# 1-Schematic_STM_CC_RAINSUN_BASICONLY.net
KiCad netlist of a schematic drawn in EasyEDA
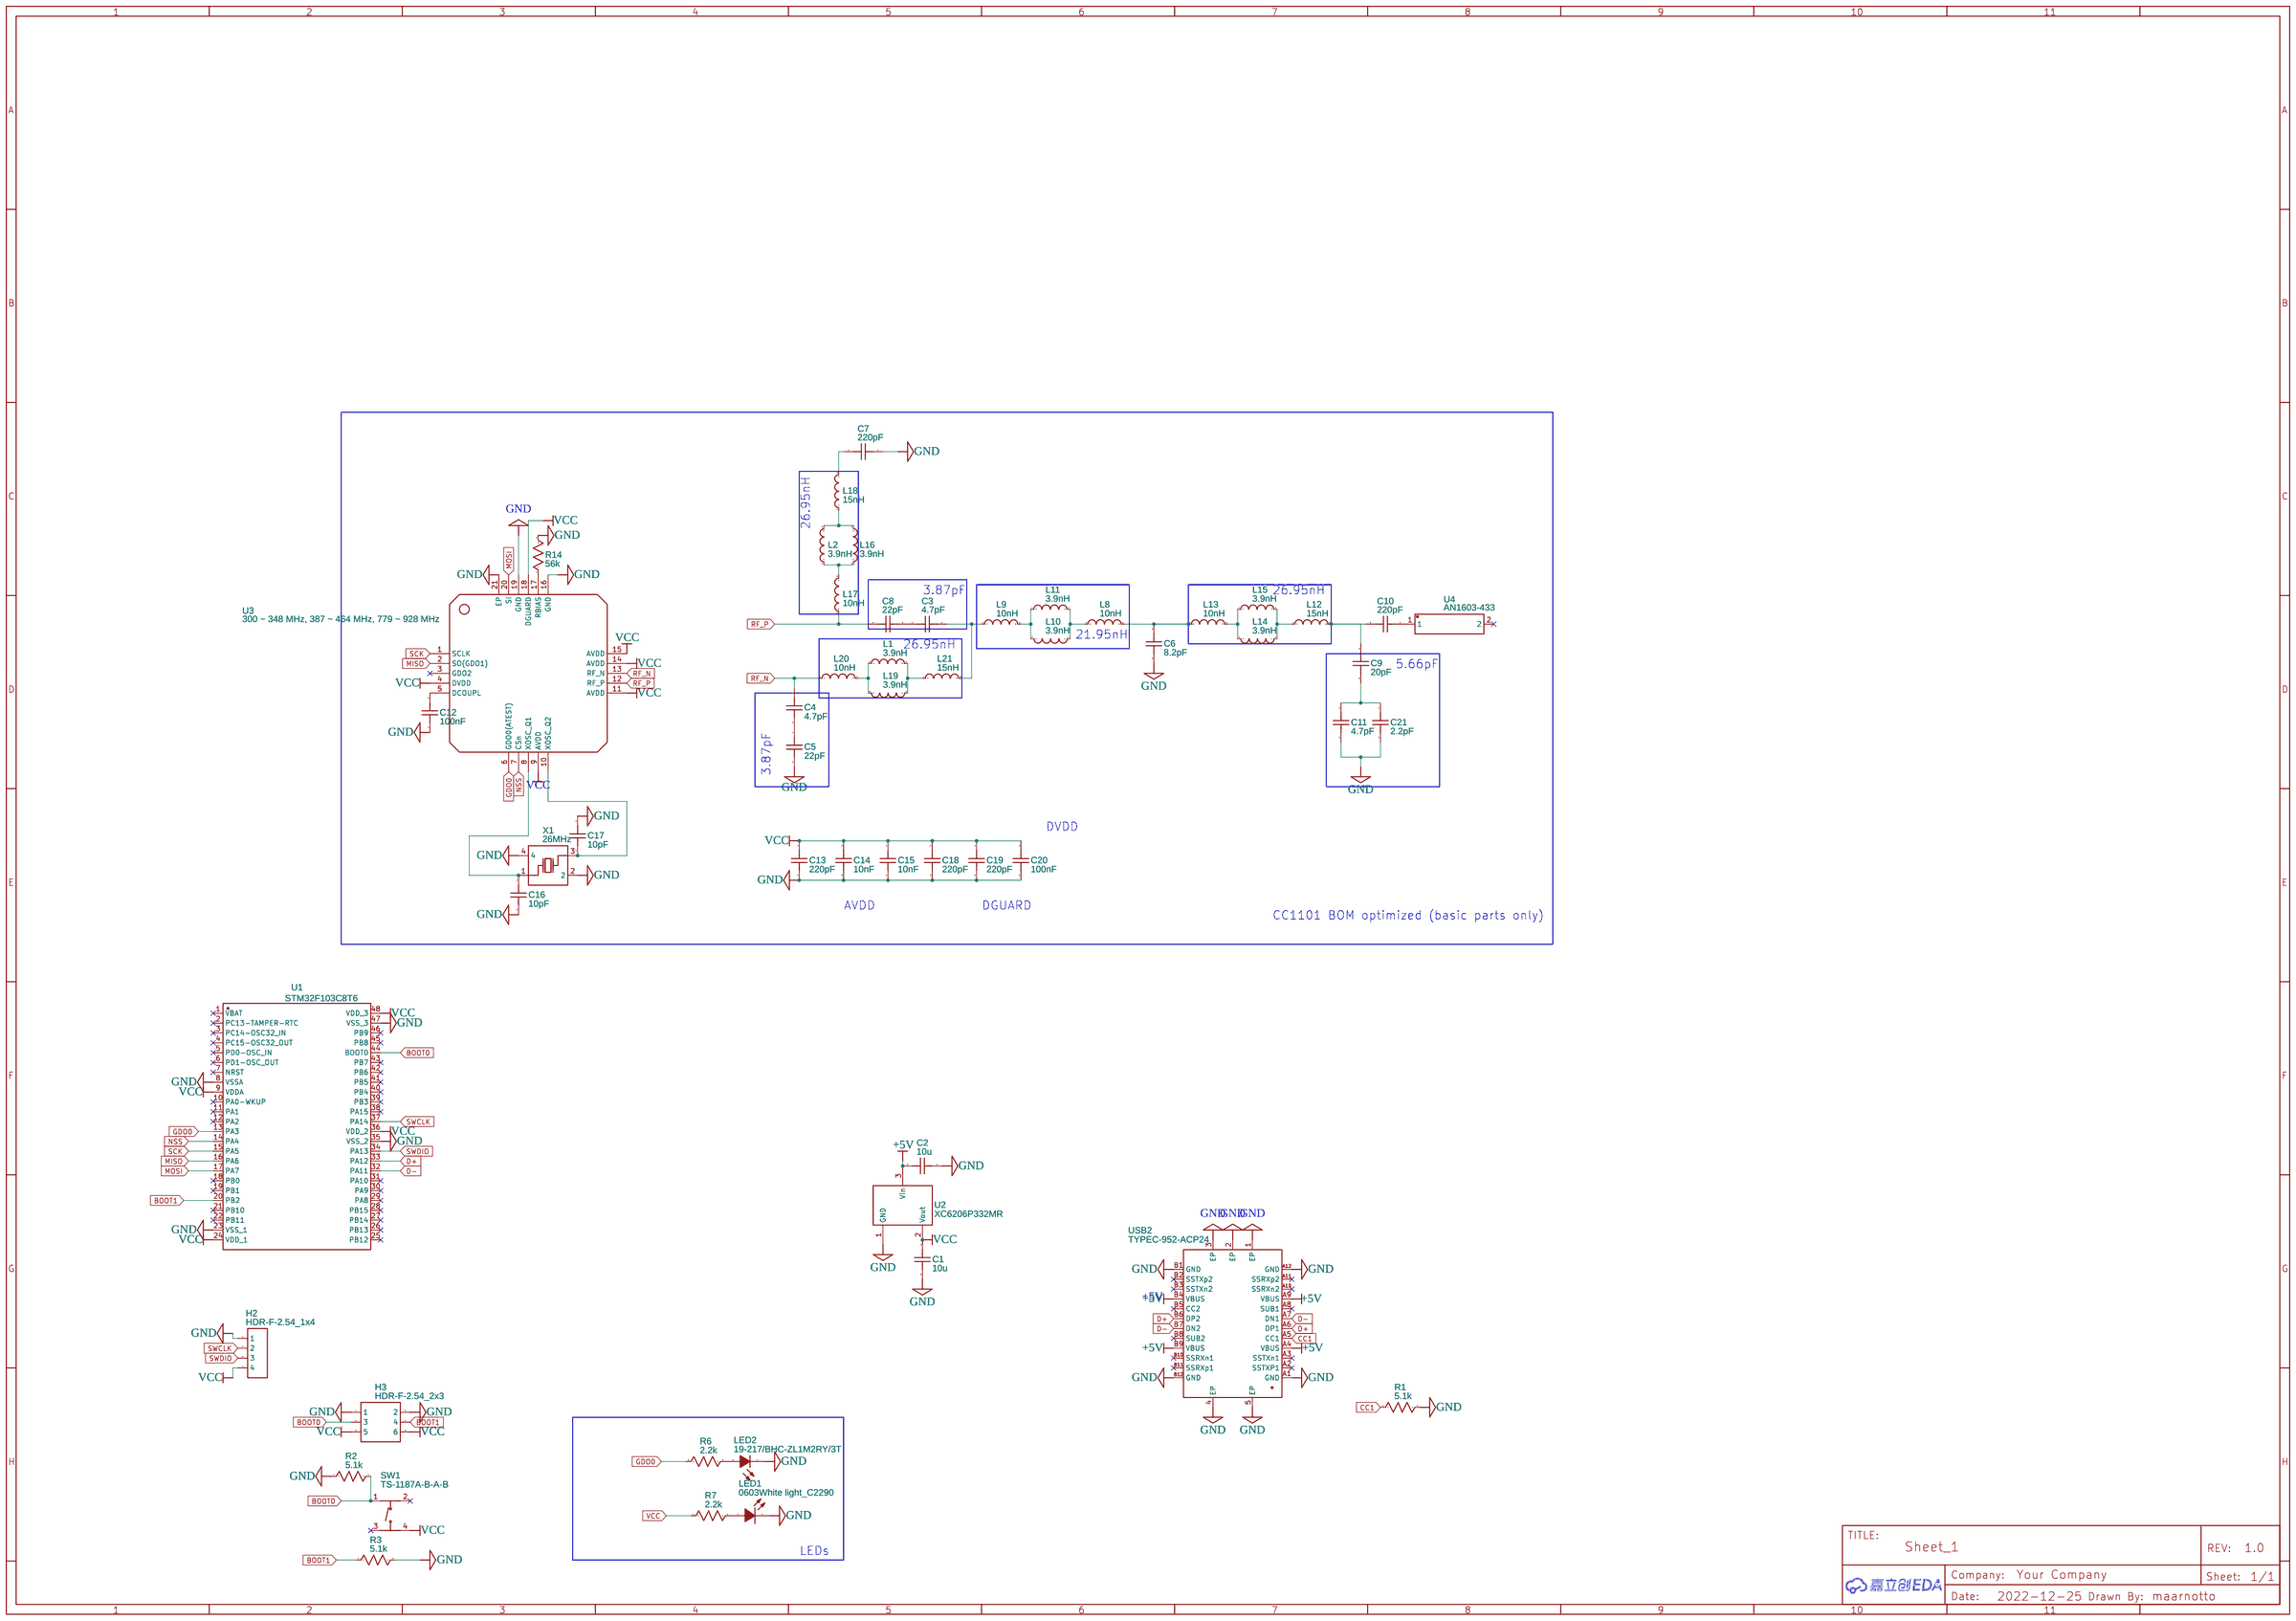
[diagram p0: schematic sheet]

(export (version "E")
  (design (tool "Eeschema 10.0.6"))
  (components
    (comp (ref "C1") (value "10u") (libsource (lib "") (part "C_0603_US")))
    (comp (ref "C2") (value "10u") (libsource (lib "") (part "C_0603_US_1")))
    (comp (ref "C3") (value "4.7pF") (libsource (lib "") (part "C_0402_US_1")))
    (comp (ref "C4") (value "4.7pF") (libsource (lib "") (part "C_0402_US")))
    (comp (ref "C5") (value "22pF") (libsource (lib "") (part "C_0402_US")))
    (comp (ref "C6") (value "8.2pF") (libsource (lib "") (part "C_0603_US")))
    (comp (ref "C7") (value "220pF") (libsource (lib "") (part "C_0402_US_1")))
    (comp (ref "C8") (value "22pF") (libsource (lib "") (part "C_0402_US_1")))
    (comp (ref "C9") (value "20pF") (libsource (lib "") (part "C_0402_US")))
    (comp (ref "C10") (value "220pF") (libsource (lib "") (part "C_0402_US_1")))
    (comp (ref "C11") (value "4.7pF") (libsource (lib "") (part "C_0402_US")))
    (comp (ref "C12") (value "100nF") (libsource (lib "") (part "C_0402_US")))
    (comp (ref "C13") (value "220pF") (libsource (lib "") (part "C_0402_US")))
    (comp (ref "C14") (value "10nF") (libsource (lib "") (part "C_0402_US")))
    (comp (ref "C15") (value "10nF") (libsource (lib "") (part "C_0402_US")))
    (comp (ref "C16") (value "10pF") (libsource (lib "") (part "C_0402_US")))
    (comp (ref "C17") (value "10pF") (libsource (lib "") (part "C_0402_US_2")))
    (comp (ref "C18") (value "220pF") (libsource (lib "") (part "C_0402_US")))
    (comp (ref "C19") (value "220pF") (libsource (lib "") (part "C_0402_US")))
    (comp (ref "C20") (value "100nF") (libsource (lib "") (part "C_0402_US")))
    (comp (ref "C21") (value "2.2pF") (libsource (lib "") (part "C_0402_US")))
    (comp (ref "H2")
      (value "HDR-F-2.54_1x4")
      (fields (field (name "BOM_Supplier Part") "C225501"))
      (libsource (lib "") (part "HDR-F-2.54_1x4"))
    )
    (comp (ref "H3")
      (value "HDR-F-2.54_2x3")
      (fields (field (name "BOM_Supplier Part") "C65114"))
      (libsource (lib "") (part "HDR-F-2.54_2x3"))
    )
    (comp (ref "L1")
      (value "3.9nH")
      (fields (field (name "BOM_Supplier Part") "C14033"))
      (libsource (lib "") (part "L0402_US_3"))
    )
    (comp (ref "L2")
      (value "3.9nH")
      (fields (field (name "BOM_Supplier Part") "C14033"))
      (libsource (lib "") (part "L0402_US_4"))
    )
    (comp (ref "L8")
      (value "10nH")
      (fields (field (name "BOM_Supplier Part") "C27147"))
      (libsource (lib "") (part "L0402_US_1"))
    )
    (comp (ref "L9")
      (value "10nH")
      (fields (field (name "BOM_Supplier Part") "C27147"))
      (libsource (lib "") (part "L0402_US_3"))
    )
    (comp (ref "L10")
      (value "3.9nH")
      (fields (field (name "BOM_Supplier Part") "C14033"))
      (libsource (lib "") (part "L0402_US"))
    )
    (comp (ref "L11")
      (value "3.9nH")
      (fields (field (name "BOM_Supplier Part") "C14033"))
      (libsource (lib "") (part "L0402_US_1"))
    )
    (comp (ref "L12")
      (value "15nH")
      (fields (field (name "BOM_Supplier Part") "C27143"))
      (libsource (lib "") (part "L0402_US_1"))
    )
    (comp (ref "L13")
      (value "10nH")
      (fields (field (name "BOM_Supplier Part") "C27147"))
      (libsource (lib "") (part "L0402_US_1"))
    )
    (comp (ref "L14")
      (value "3.9nH")
      (fields (field (name "BOM_Supplier Part") "C14033"))
      (libsource (lib "") (part "L0402_US"))
    )
    (comp (ref "L15")
      (value "3.9nH")
      (fields (field (name "BOM_Supplier Part") "C14033"))
      (libsource (lib "") (part "L0402_US_1"))
    )
    (comp (ref "L16")
      (value "3.9nH")
      (fields (field (name "BOM_Supplier Part") "C14033"))
      (libsource (lib "") (part "L0402_US_2"))
    )
    (comp (ref "L17")
      (value "10nH")
      (fields (field (name "BOM_Supplier Part") "C27147"))
      (libsource (lib "") (part "L0402_US_4"))
    )
    (comp (ref "L18")
      (value "15nH")
      (fields (field (name "BOM_Supplier Part") "C27143"))
      (libsource (lib "") (part "L0402_US_4"))
    )
    (comp (ref "L19")
      (value "3.9nH")
      (fields (field (name "BOM_Supplier Part") "C14033"))
      (libsource (lib "") (part "L0402_US_5"))
    )
    (comp (ref "L20")
      (value "10nH")
      (fields (field (name "BOM_Supplier Part") "C27147"))
      (libsource (lib "") (part "L0402_US_3"))
    )
    (comp (ref "L21")
      (value "15nH")
      (fields (field (name "BOM_Supplier Part") "C27143"))
      (libsource (lib "") (part "L0402_US_3"))
    )
    (comp (ref "LED1")
      (value "0603White light_C2290")
      (fields (field (name "BOM_Manufacturer Part") "KT-0603白灯") (field (name "BOM_Supplier Part") "C2290"))
      (libsource (lib "") (part "0603White light_C2290"))
    )
    (comp (ref "LED2")
      (value "19-217/BHC-ZL1M2RY/3T")
      (fields (field (name "BOM_Supplier Part") "C72041"))
      (libsource (lib "") (part "19-217/BHC-ZL1M2RY/3T"))
    )
    (comp (ref "R1") (value "5.1k") (libsource (lib "") (part "R_0603_US")))
    (comp (ref "R2") (value "5.1k") (libsource (lib "") (part "R_0603_US")))
    (comp (ref "R3") (value "5.1k") (libsource (lib "") (part "R_0603_US")))
    (comp (ref "R6") (value "2.2k") (libsource (lib "") (part "R_0603_US")))
    (comp (ref "R7") (value "2.2k") (libsource (lib "") (part "R_0603_US")))
    (comp (ref "R14") (value "56k") (libsource (lib "") (part "R_0402_US")))
    (comp (ref "SW1")
      (value "TS-1187A-B-A-B")
      (fields (field (name "BOM_Supplier Part") "C318884"))
      (libsource (lib "") (part "TS-1187A-B-A-B"))
    )
    (comp (ref "U1")
      (value "STM32F103C8T6")
      (fields (field (name "BOM_Supplier Part") "C8734"))
      (libsource (lib "") (part "STM32F103C8T6"))
    )
    (comp (ref "U2")
      (value "XC6206P332MR")
      (fields (field (name "BOM_Supplier Part") "C5446"))
      (libsource (lib "") (part "XC6206P332MR"))
    )
    (comp (ref "U3")
      (value "300 ~ 348 MHz, 387 ~ 464 MHz, 779 ~ 928 MHz")
      (fields (field (name "BOM_Manufacturer Part") "CC1101RGPR") (field (name "BOM_Supplier Part") "C29953"))
      (libsource (lib "") (part "CC1101RGPR"))
    )
    (comp (ref "U4")
      (value "AN1603-433")
      (fields (field (name "BOM_Supplier Part") "C122806"))
      (libsource (lib "") (part "AN1603-433"))
    )
    (comp (ref "USB2")
      (value "TYPEC-952-ACP24")
      (fields (field (name "BOM_Supplier Part") "C2840398"))
      (libsource (lib "") (part "TYPEC-952-ACP24"))
    )
    (comp (ref "X1")
      (value "26MHz")
      (fields
        (field (name "BOM_Manufacturer Part") "3S26000333")
        (field (name "BOM_Supplier Part") "C431163")
      )
      (libsource (lib "") (part "3S26000333"))
    )
  )
  (nets
    (net (code "1") (name "+5V") (class "Default")
      (node (ref "C2") (pin "2") (pinfunction "2_2") (pintype "unspecified"))
      (node (ref "U2") (pin "3") (pinfunction "Vin_3") (pintype "unspecified"))
      (node (ref "USB2") (pin "A4") (pinfunction "VBUS_A4") (pintype "unspecified"))
      (node (ref "USB2") (pin "A9") (pinfunction "VBUS_A9") (pintype "unspecified"))
      (node (ref "USB2") (pin "B4") (pinfunction "VBUS_B4") (pintype "unspecified"))
      (node (ref "USB2") (pin "B9") (pinfunction "VBUS_B9") (pintype "unspecified"))
    )
    (net (code "2") (name "BOOT0") (class "Default")
      (node (ref "H3") (pin "3") (pinfunction "3_3") (pintype "input"))
      (node (ref "R2") (pin "2") (pinfunction "2_2") (pintype "unspecified"))
      (node (ref "SW1") (pin "1") (pinfunction "A_1") (pintype "unspecified"))
      (node (ref "U1") (pin "44") (pinfunction "BOOT0_44") (pintype "unspecified"))
    )
    (net (code "3") (name "BOOT1") (class "Default")
      (node (ref "H3") (pin "4") (pinfunction "4_4") (pintype "input"))
      (node (ref "R3") (pin "1") (pinfunction "1_1") (pintype "unspecified"))
      (node (ref "U1") (pin "20") (pinfunction "PB2_20") (pintype "unspecified"))
    )
    (net (code "4") (name "CC1") (class "Default")
      (node (ref "R1") (pin "1") (pinfunction "1_1") (pintype "unspecified"))
      (node (ref "USB2") (pin "A5") (pinfunction "CC1_A5") (pintype "unspecified"))
    )
    (net (code "5") (name "D+") (class "Default")
      (node (ref "U1") (pin "33") (pinfunction "PA12_33") (pintype "unspecified"))
      (node (ref "USB2") (pin "A6") (pinfunction "DP1_A6") (pintype "unspecified"))
      (node (ref "USB2") (pin "B6") (pinfunction "DP2_B6") (pintype "unspecified"))
    )
    (net (code "6") (name "D-") (class "Default")
      (node (ref "U1") (pin "32") (pinfunction "PA11_32") (pintype "unspecified"))
      (node (ref "USB2") (pin "A7") (pinfunction "DN1_A7") (pintype "unspecified"))
      (node (ref "USB2") (pin "B7") (pinfunction "DN2_B7") (pintype "unspecified"))
    )
    (net (code "7") (name "GDO0") (class "Default")
      (node (ref "R6") (pin "1") (pinfunction "1_1") (pintype "unspecified"))
      (node (ref "U1") (pin "13") (pinfunction "PA3_13") (pintype "unspecified"))
      (node (ref "U3") (pin "6") (pinfunction "GDO0(ATEST)_6") (pintype "unspecified"))
    )
    (net (code "8") (name "GND") (class "Default")
      (node (ref "C1") (pin "2") (pinfunction "2_2") (pintype "unspecified"))
      (node (ref "C11") (pin "2") (pinfunction "2_2") (pintype "unspecified"))
      (node (ref "C12") (pin "2") (pinfunction "2_2") (pintype "unspecified"))
      (node (ref "C13") (pin "2") (pinfunction "2_2") (pintype "unspecified"))
      (node (ref "C14") (pin "2") (pinfunction "2_2") (pintype "unspecified"))
      (node (ref "C15") (pin "2") (pinfunction "2_2") (pintype "unspecified"))
      (node (ref "C16") (pin "2") (pinfunction "2_2") (pintype "unspecified"))
      (node (ref "C17") (pin "2") (pinfunction "2_2") (pintype "unspecified"))
      (node (ref "C18") (pin "2") (pinfunction "2_2") (pintype "unspecified"))
      (node (ref "C19") (pin "2") (pinfunction "2_2") (pintype "unspecified"))
      (node (ref "C2") (pin "1") (pinfunction "1_1") (pintype "unspecified"))
      (node (ref "C20") (pin "2") (pinfunction "2_2") (pintype "unspecified"))
      (node (ref "C21") (pin "2") (pinfunction "2_2") (pintype "unspecified"))
      (node (ref "C5") (pin "2") (pinfunction "2_2") (pintype "unspecified"))
      (node (ref "C6") (pin "2") (pinfunction "2_2") (pintype "unspecified"))
      (node (ref "C7") (pin "1") (pinfunction "1_1") (pintype "unspecified"))
      (node (ref "H2") (pin "1") (pinfunction "1_1") (pintype "unspecified"))
      (node (ref "H3") (pin "1") (pinfunction "1_1") (pintype "input"))
      (node (ref "H3") (pin "2") (pinfunction "2_2") (pintype "input"))
      (node (ref "LED1") (pin "2") (pinfunction "K_2") (pintype "unspecified"))
      (node (ref "LED2") (pin "1") (pinfunction "C_1") (pintype "input"))
      (node (ref "R1") (pin "2") (pinfunction "2_2") (pintype "unspecified"))
      (node (ref "R14") (pin "2") (pinfunction "2_2") (pintype "unspecified"))
      (node (ref "R2") (pin "1") (pinfunction "1_1") (pintype "unspecified"))
      (node (ref "R3") (pin "2") (pinfunction "2_2") (pintype "unspecified"))
      (node (ref "U1") (pin "23") (pinfunction "VSS_1_23") (pintype "unspecified"))
      (node (ref "U1") (pin "35") (pinfunction "VSS_2_35") (pintype "unspecified"))
      (node (ref "U1") (pin "47") (pinfunction "VSS_3_47") (pintype "unspecified"))
      (node (ref "U1") (pin "8") (pinfunction "VSSA_8") (pintype "unspecified"))
      (node (ref "U2") (pin "1") (pinfunction "GND_1") (pintype "unspecified"))
      (node (ref "U3") (pin "16") (pinfunction "GND_16") (pintype "unspecified"))
      (node (ref "U3") (pin "19") (pinfunction "GND_19") (pintype "unspecified"))
      (node (ref "U3") (pin "21") (pinfunction "EP_21") (pintype "unspecified"))
      (node (ref "USB2") (pin "1") (pinfunction "EP_1") (pintype "unspecified"))
      (node (ref "USB2") (pin "2") (pinfunction "EP_2") (pintype "unspecified"))
      (node (ref "USB2") (pin "3") (pinfunction "EP_3") (pintype "unspecified"))
      (node (ref "USB2") (pin "4") (pinfunction "EP_4") (pintype "unspecified"))
      (node (ref "USB2") (pin "5") (pinfunction "EP_5") (pintype "unspecified"))
      (node (ref "USB2") (pin "A1") (pinfunction "GND_A1") (pintype "unspecified"))
      (node (ref "USB2") (pin "A12") (pinfunction "GND_A12") (pintype "unspecified"))
      (node (ref "USB2") (pin "B1") (pinfunction "GND_B1") (pintype "unspecified"))
      (node (ref "USB2") (pin "B12") (pinfunction "GND_B12") (pintype "unspecified"))
      (node (ref "X1") (pin "2") (pinfunction "2_2") (pintype "unspecified"))
      (node (ref "X1") (pin "4") (pinfunction "4_4") (pintype "unspecified"))
    )
    (net (code "9") (name "MISO") (class "Default")
      (node (ref "U1") (pin "16") (pinfunction "PA6_16") (pintype "unspecified"))
      (node (ref "U3") (pin "2") (pinfunction "SO(GDO1)_2") (pintype "unspecified"))
    )
    (net (code "10") (name "MOSI") (class "Default")
      (node (ref "U1") (pin "17") (pinfunction "PA7_17") (pintype "unspecified"))
      (node (ref "U3") (pin "20") (pinfunction "SI_20") (pintype "unspecified"))
    )
    (net (code "11") (name "NSS") (class "Default")
      (node (ref "U1") (pin "14") (pinfunction "PA4_14") (pintype "unspecified"))
      (node (ref "U3") (pin "7") (pinfunction "CSn_7") (pintype "unspecified"))
    )
    (net (code "12") (name "Net-(C3-Pad1)") (class "Default")
      (node (ref "C3") (pin "1") (pinfunction "1_1") (pintype "unspecified"))
      (node (ref "L21") (pin "2") (pinfunction "2_2") (pintype "unspecified"))
      (node (ref "L9") (pin "1") (pinfunction "1_1") (pintype "unspecified"))
    )
    (net (code "13") (name "Net-(C3-Pad2)") (class "Default")
      (node (ref "C3") (pin "2") (pinfunction "2_2") (pintype "unspecified"))
      (node (ref "C8") (pin "1") (pinfunction "1_1") (pintype "unspecified"))
    )
    (net (code "14") (name "Net-(C4-Pad2)") (class "Default")
      (node (ref "C4") (pin "2") (pinfunction "2_2") (pintype "unspecified"))
      (node (ref "C5") (pin "1") (pinfunction "1_1") (pintype "unspecified"))
    )
    (net (code "15") (name "Net-(C6-Pad1)") (class "Default")
      (node (ref "C6") (pin "1") (pinfunction "1_1") (pintype "unspecified"))
      (node (ref "L13") (pin "1") (pinfunction "1_1") (pintype "unspecified"))
      (node (ref "L8") (pin "2") (pinfunction "2_2") (pintype "unspecified"))
    )
    (net (code "16") (name "Net-(C7-Pad2)") (class "Default")
      (node (ref "C7") (pin "2") (pinfunction "2_2") (pintype "unspecified"))
      (node (ref "L18") (pin "2") (pinfunction "2_2") (pintype "unspecified"))
    )
    (net (code "17") (name "Net-(C10-Pad1)") (class "Default")
      (node (ref "C10") (pin "1") (pinfunction "1_1") (pintype "unspecified"))
      (node (ref "U4") (pin "1") (pinfunction "1_1") (pintype "unspecified"))
    )
    (net (code "18") (name "Net-(C10-Pad2)") (class "Default")
      (node (ref "C10") (pin "2") (pinfunction "2_2") (pintype "unspecified"))
      (node (ref "C9") (pin "1") (pinfunction "1_1") (pintype "unspecified"))
      (node (ref "L12") (pin "2") (pinfunction "2_2") (pintype "unspecified"))
    )
    (net (code "19") (name "Net-(C11-Pad1)") (class "Default")
      (node (ref "C11") (pin "1") (pinfunction "1_1") (pintype "unspecified"))
      (node (ref "C21") (pin "1") (pinfunction "1_1") (pintype "unspecified"))
      (node (ref "C9") (pin "2") (pinfunction "2_2") (pintype "unspecified"))
    )
    (net (code "20") (name "Net-(L1-Pad1)") (class "Default")
      (node (ref "L1") (pin "1") (pinfunction "1_1") (pintype "unspecified"))
      (node (ref "L19") (pin "2") (pinfunction "2_2") (pintype "unspecified"))
      (node (ref "L20") (pin "2") (pinfunction "2_2") (pintype "unspecified"))
    )
    (net (code "21") (name "Net-(L1-Pad2)") (class "Default")
      (node (ref "L1") (pin "2") (pinfunction "2_2") (pintype "unspecified"))
      (node (ref "L19") (pin "1") (pinfunction "1_1") (pintype "unspecified"))
      (node (ref "L21") (pin "1") (pinfunction "1_1") (pintype "unspecified"))
    )
    (net (code "22") (name "Net-(L10-Pad1)") (class "Default")
      (node (ref "L10") (pin "1") (pinfunction "1_1") (pintype "unspecified"))
      (node (ref "L11") (pin "2") (pinfunction "2_2") (pintype "unspecified"))
      (node (ref "L8") (pin "1") (pinfunction "1_1") (pintype "unspecified"))
    )
    (net (code "23") (name "Net-(L10-Pad2)") (class "Default")
      (node (ref "L10") (pin "2") (pinfunction "2_2") (pintype "unspecified"))
      (node (ref "L11") (pin "1") (pinfunction "1_1") (pintype "unspecified"))
      (node (ref "L9") (pin "2") (pinfunction "2_2") (pintype "unspecified"))
    )
    (net (code "24") (name "Net-(L12-Pad1)") (class "Default")
      (node (ref "L12") (pin "1") (pinfunction "1_1") (pintype "unspecified"))
      (node (ref "L14") (pin "1") (pinfunction "1_1") (pintype "unspecified"))
      (node (ref "L15") (pin "2") (pinfunction "2_2") (pintype "unspecified"))
    )
    (net (code "25") (name "Net-(L13-Pad2)") (class "Default")
      (node (ref "L13") (pin "2") (pinfunction "2_2") (pintype "unspecified"))
      (node (ref "L14") (pin "2") (pinfunction "2_2") (pintype "unspecified"))
      (node (ref "L15") (pin "1") (pinfunction "1_1") (pintype "unspecified"))
    )
    (net (code "26") (name "Net-(L16-Pad1)") (class "Default")
      (node (ref "L16") (pin "1") (pinfunction "1_1") (pintype "unspecified"))
      (node (ref "L18") (pin "1") (pinfunction "1_1") (pintype "unspecified"))
      (node (ref "L2") (pin "2") (pinfunction "2_2") (pintype "unspecified"))
    )
    (net (code "27") (name "Net-(L16-Pad2)") (class "Default")
      (node (ref "L16") (pin "2") (pinfunction "2_2") (pintype "unspecified"))
      (node (ref "L17") (pin "2") (pinfunction "2_2") (pintype "unspecified"))
      (node (ref "L2") (pin "1") (pinfunction "1_1") (pintype "unspecified"))
    )
    (net (code "28") (name "Net-(LED1-A)") (class "Default")
      (node (ref "LED1") (pin "1") (pinfunction "A_1") (pintype "unspecified"))
      (node (ref "R7") (pin "2") (pinfunction "2_2") (pintype "unspecified"))
    )
    (net (code "29") (name "Net-(LED2-A)") (class "Default")
      (node (ref "LED2") (pin "2") (pinfunction "A_2") (pintype "input"))
      (node (ref "R6") (pin "2") (pinfunction "2_2") (pintype "unspecified"))
    )
    (net (code "30") (name "Net-(U3-DCOUPL)") (class "Default")
      (node (ref "C12") (pin "1") (pinfunction "1_1") (pintype "unspecified"))
      (node (ref "U3") (pin "5") (pinfunction "DCOUPL_5") (pintype "unspecified"))
    )
    (net (code "31") (name "Net-(U3-RBIAS)") (class "Default")
      (node (ref "R14") (pin "1") (pinfunction "1_1") (pintype "unspecified"))
      (node (ref "U3") (pin "17") (pinfunction "RBIAS_17") (pintype "unspecified"))
    )
    (net (code "32") (name "Net-(U3-XOSC_Q1)") (class "Default")
      (node (ref "C16") (pin "1") (pinfunction "1_1") (pintype "unspecified"))
      (node (ref "U3") (pin "8") (pinfunction "XOSC_Q1_8") (pintype "unspecified"))
      (node (ref "X1") (pin "1") (pinfunction "OSC1_1") (pintype "unspecified"))
    )
    (net (code "33") (name "Net-(U3-XOSC_Q2)") (class "Default")
      (node (ref "C17") (pin "1") (pinfunction "1_1") (pintype "unspecified"))
      (node (ref "U3") (pin "10") (pinfunction "XOSC_Q2_10") (pintype "unspecified"))
      (node (ref "X1") (pin "3") (pinfunction "OSC2_3") (pintype "unspecified"))
    )
    (net (code "34") (name "RF_N") (class "Default")
      (node (ref "C4") (pin "1") (pinfunction "1_1") (pintype "unspecified"))
      (node (ref "L20") (pin "1") (pinfunction "1_1") (pintype "unspecified"))
      (node (ref "U3") (pin "13") (pinfunction "RF_N_13") (pintype "unspecified"))
    )
    (net (code "35") (name "RF_P") (class "Default")
      (node (ref "C8") (pin "2") (pinfunction "2_2") (pintype "unspecified"))
      (node (ref "L17") (pin "1") (pinfunction "1_1") (pintype "unspecified"))
      (node (ref "U3") (pin "12") (pinfunction "RF_P_12") (pintype "unspecified"))
    )
    (net (code "36") (name "SCK") (class "Default")
      (node (ref "U1") (pin "15") (pinfunction "PA5_15") (pintype "unspecified"))
      (node (ref "U3") (pin "1") (pinfunction "SCLK_1") (pintype "unspecified"))
    )
    (net (code "37") (name "SWCLK") (class "Default")
      (node (ref "H2") (pin "2") (pinfunction "2_2") (pintype "unspecified"))
      (node (ref "U1") (pin "37") (pinfunction "PA14_37") (pintype "unspecified"))
    )
    (net (code "38") (name "SWDIO") (class "Default")
      (node (ref "H2") (pin "3") (pinfunction "3_3") (pintype "unspecified"))
      (node (ref "U1") (pin "34") (pinfunction "PA13_34") (pintype "unspecified"))
    )
    (net (code "39") (name "VCC") (class "Default")
      (node (ref "C1") (pin "1") (pinfunction "1_1") (pintype "unspecified"))
      (node (ref "C13") (pin "1") (pinfunction "1_1") (pintype "unspecified"))
      (node (ref "C14") (pin "1") (pinfunction "1_1") (pintype "unspecified"))
      (node (ref "C15") (pin "1") (pinfunction "1_1") (pintype "unspecified"))
      (node (ref "C18") (pin "1") (pinfunction "1_1") (pintype "unspecified"))
      (node (ref "C19") (pin "1") (pinfunction "1_1") (pintype "unspecified"))
      (node (ref "C20") (pin "1") (pinfunction "1_1") (pintype "unspecified"))
      (node (ref "H2") (pin "4") (pinfunction "4_4") (pintype "unspecified"))
      (node (ref "H3") (pin "5") (pinfunction "5_5") (pintype "input"))
      (node (ref "H3") (pin "6") (pinfunction "6_6") (pintype "input"))
      (node (ref "R7") (pin "1") (pinfunction "1_1") (pintype "unspecified"))
      (node (ref "SW1") (pin "4") (pinfunction "D_4") (pintype "unspecified"))
      (node (ref "U1") (pin "24") (pinfunction "VDD_1_24") (pintype "unspecified"))
      (node (ref "U1") (pin "36") (pinfunction "VDD_2_36") (pintype "unspecified"))
      (node (ref "U1") (pin "48") (pinfunction "VDD_3_48") (pintype "unspecified"))
      (node (ref "U1") (pin "9") (pinfunction "VDDA_9") (pintype "unspecified"))
      (node (ref "U2") (pin "2") (pinfunction "Vout_2") (pintype "unspecified"))
      (node (ref "U3") (pin "11") (pinfunction "AVDD_11") (pintype "unspecified"))
      (node (ref "U3") (pin "14") (pinfunction "AVDD_14") (pintype "unspecified"))
      (node (ref "U3") (pin "15") (pinfunction "AVDD_15") (pintype "unspecified"))
      (node (ref "U3") (pin "18") (pinfunction "DGUARD_18") (pintype "unspecified"))
      (node (ref "U3") (pin "4") (pinfunction "DVDD_4") (pintype "unspecified"))
      (node (ref "U3") (pin "9") (pinfunction "AVDD_9") (pintype "unspecified"))
    )
    (net (code "40") (name "unconnected-(SW1-B-Pad2)") (class "Default")
      (node (ref "SW1") (pin "2") (pinfunction "B_2") (pintype "unspecified+no_connect"))
    )
    (net (code "41") (name "unconnected-(SW1-C-Pad3)") (class "Default")
      (node (ref "SW1") (pin "3") (pinfunction "C_3") (pintype "unspecified+no_connect"))
    )
    (net (code "42") (name "unconnected-(U1-NRST-Pad7)") (class "Default")
      (node (ref "U1") (pin "7") (pinfunction "NRST_7") (pintype "unspecified+no_connect"))
    )
    (net (code "43") (name "unconnected-(U1-PA0-WKUP-Pad10)") (class "Default")
      (node (ref "U1") (pin "10") (pinfunction "PA0-WKUP_10") (pintype "unspecified+no_connect"))
    )
    (net (code "44") (name "unconnected-(U1-PA1-Pad11)") (class "Default")
      (node (ref "U1") (pin "11") (pinfunction "PA1_11") (pintype "unspecified+no_connect"))
    )
    (net (code "45") (name "unconnected-(U1-PA2-Pad12)") (class "Default")
      (node (ref "U1") (pin "12") (pinfunction "PA2_12") (pintype "unspecified+no_connect"))
    )
    (net (code "46") (name "unconnected-(U1-PA8-Pad29)") (class "Default")
      (node (ref "U1") (pin "29") (pinfunction "PA8_29") (pintype "unspecified+no_connect"))
    )
    (net (code "47") (name "unconnected-(U1-PA9-Pad30)") (class "Default")
      (node (ref "U1") (pin "30") (pinfunction "PA9_30") (pintype "unspecified+no_connect"))
    )
    (net (code "48") (name "unconnected-(U1-PA10-Pad31)") (class "Default")
      (node (ref "U1") (pin "31") (pinfunction "PA10_31") (pintype "unspecified+no_connect"))
    )
    (net (code "49") (name "unconnected-(U1-PA15-Pad38)") (class "Default")
      (node (ref "U1") (pin "38") (pinfunction "PA15_38") (pintype "unspecified+no_connect"))
    )
    (net (code "50") (name "unconnected-(U1-PB0-Pad18)") (class "Default")
      (node (ref "U1") (pin "18") (pinfunction "PB0_18") (pintype "unspecified+no_connect"))
    )
    (net (code "51") (name "unconnected-(U1-PB1-Pad19)") (class "Default")
      (node (ref "U1") (pin "19") (pinfunction "PB1_19") (pintype "unspecified+no_connect"))
    )
    (net (code "52") (name "unconnected-(U1-PB3-Pad39)") (class "Default")
      (node (ref "U1") (pin "39") (pinfunction "PB3_39") (pintype "unspecified+no_connect"))
    )
    (net (code "53") (name "unconnected-(U1-PB4-Pad40)") (class "Default")
      (node (ref "U1") (pin "40") (pinfunction "PB4_40") (pintype "unspecified+no_connect"))
    )
    (net (code "54") (name "unconnected-(U1-PB5-Pad41)") (class "Default")
      (node (ref "U1") (pin "41") (pinfunction "PB5_41") (pintype "unspecified+no_connect"))
    )
    (net (code "55") (name "unconnected-(U1-PB6-Pad42)") (class "Default")
      (node (ref "U1") (pin "42") (pinfunction "PB6_42") (pintype "unspecified+no_connect"))
    )
    (net (code "56") (name "unconnected-(U1-PB7-Pad43)") (class "Default")
      (node (ref "U1") (pin "43") (pinfunction "PB7_43") (pintype "unspecified+no_connect"))
    )
    (net (code "57") (name "unconnected-(U1-PB8-Pad45)") (class "Default")
      (node (ref "U1") (pin "45") (pinfunction "PB8_45") (pintype "unspecified+no_connect"))
    )
    (net (code "58") (name "unconnected-(U1-PB9-Pad46)") (class "Default")
      (node (ref "U1") (pin "46") (pinfunction "PB9_46") (pintype "unspecified+no_connect"))
    )
    (net (code "59") (name "unconnected-(U1-PB10-Pad21)") (class "Default")
      (node (ref "U1") (pin "21") (pinfunction "PB10_21") (pintype "unspecified+no_connect"))
    )
    (net (code "60") (name "unconnected-(U1-PB11-Pad22)") (class "Default")
      (node (ref "U1") (pin "22") (pinfunction "PB11_22") (pintype "unspecified+no_connect"))
    )
    (net (code "61") (name "unconnected-(U1-PB12-Pad25)") (class "Default")
      (node (ref "U1") (pin "25") (pinfunction "PB12_25") (pintype "unspecified+no_connect"))
    )
    (net (code "62") (name "unconnected-(U1-PB13-Pad26)") (class "Default")
      (node (ref "U1") (pin "26") (pinfunction "PB13_26") (pintype "unspecified+no_connect"))
    )
    (net (code "63") (name "unconnected-(U1-PB14-Pad27)") (class "Default")
      (node (ref "U1") (pin "27") (pinfunction "PB14_27") (pintype "unspecified+no_connect"))
    )
    (net (code "64") (name "unconnected-(U1-PB15-Pad28)") (class "Default")
      (node (ref "U1") (pin "28") (pinfunction "PB15_28") (pintype "unspecified+no_connect"))
    )
    (net (code "65") (name "unconnected-(U1-PC13-TAMPER-RTC-Pad2)") (class "Default")
      (node (ref "U1") (pin "2") (pinfunction "PC13-TAMPER-RTC_2") (pintype "unspecified+no_connect"))
    )
    (net (code "66") (name "unconnected-(U1-PC14-OSC32_IN-Pad3)") (class "Default")
      (node (ref "U1") (pin "3") (pinfunction "PC14-OSC32_IN_3") (pintype "unspecified+no_connect"))
    )
    (net (code "67") (name "unconnected-(U1-PC15-OSC32_OUT-Pad4)") (class "Default")
      (node (ref "U1") (pin "4") (pinfunction "PC15-OSC32_OUT_4") (pintype "unspecified+no_connect"))
    )
    (net (code "68") (name "unconnected-(U1-PD0-OSC_IN-Pad5)") (class "Default")
      (node (ref "U1") (pin "5") (pinfunction "PD0-OSC_IN_5") (pintype "unspecified+no_connect"))
    )
    (net (code "69") (name "unconnected-(U1-PD1-OSC_OUT-Pad6)") (class "Default")
      (node (ref "U1") (pin "6") (pinfunction "PD1-OSC_OUT_6") (pintype "unspecified+no_connect"))
    )
    (net (code "70") (name "unconnected-(U1-VBAT-Pad1)") (class "Default")
      (node (ref "U1") (pin "1") (pinfunction "VBAT_1") (pintype "unspecified+no_connect"))
    )
    (net (code "71") (name "unconnected-(U3-GDO2-Pad3)") (class "Default")
      (node (ref "U3") (pin "3") (pinfunction "GDO2_3") (pintype "unspecified+no_connect"))
    )
    (net (code "72") (name "unconnected-(U4-Pad2)") (class "Default")
      (node (ref "U4") (pin "2") (pinfunction "2_2") (pintype "unspecified+no_connect"))
    )
    (net (code "73") (name "unconnected-(USB2-CC2-PadB5)") (class "Default")
      (node (ref "USB2") (pin "B5") (pinfunction "CC2_B5") (pintype "unspecified+no_connect"))
    )
    (net (code "74") (name "unconnected-(USB2-SSRXn1-PadB10)") (class "Default")
      (node (ref "USB2") (pin "B10") (pinfunction "SSRXn1_B10") (pintype "unspecified+no_connect"))
    )
    (net (code "75") (name "unconnected-(USB2-SSRXn2-PadA10)") (class "Default")
      (node (ref "USB2") (pin "A10") (pinfunction "SSRXn2_A10") (pintype "unspecified+no_connect"))
    )
    (net (code "76") (name "unconnected-(USB2-SSRXp1-PadB11)") (class "Default")
      (node (ref "USB2") (pin "B11") (pinfunction "SSRXp1_B11") (pintype "unspecified+no_connect"))
    )
    (net (code "77") (name "unconnected-(USB2-SSRXp2-PadA11)") (class "Default")
      (node (ref "USB2") (pin "A11") (pinfunction "SSRXp2_A11") (pintype "unspecified+no_connect"))
    )
    (net (code "78") (name "unconnected-(USB2-SSTXP1-PadA2)") (class "Default")
      (node (ref "USB2") (pin "A2") (pinfunction "SSTXP1_A2") (pintype "unspecified+no_connect"))
    )
    (net (code "79") (name "unconnected-(USB2-SSTXn1-PadA3)") (class "Default")
      (node (ref "USB2") (pin "A3") (pinfunction "SSTXn1_A3") (pintype "unspecified+no_connect"))
    )
    (net (code "80") (name "unconnected-(USB2-SSTXn2-PadB3)") (class "Default")
      (node (ref "USB2") (pin "B3") (pinfunction "SSTXn2_B3") (pintype "unspecified+no_connect"))
    )
    (net (code "81") (name "unconnected-(USB2-SSTXp2-PadB2)") (class "Default")
      (node (ref "USB2") (pin "B2") (pinfunction "SSTXp2_B2") (pintype "unspecified+no_connect"))
    )
    (net (code "82") (name "unconnected-(USB2-SUB1-PadA8)") (class "Default")
      (node (ref "USB2") (pin "A8") (pinfunction "SUB1_A8") (pintype "unspecified+no_connect"))
    )
    (net (code "83") (name "unconnected-(USB2-SUB2-PadB8)") (class "Default")
      (node (ref "USB2") (pin "B8") (pinfunction "SUB2_B8") (pintype "unspecified+no_connect"))
    )
  )
)
